# angle.net
KiCad netlist of a schematic drawn in EAGLE
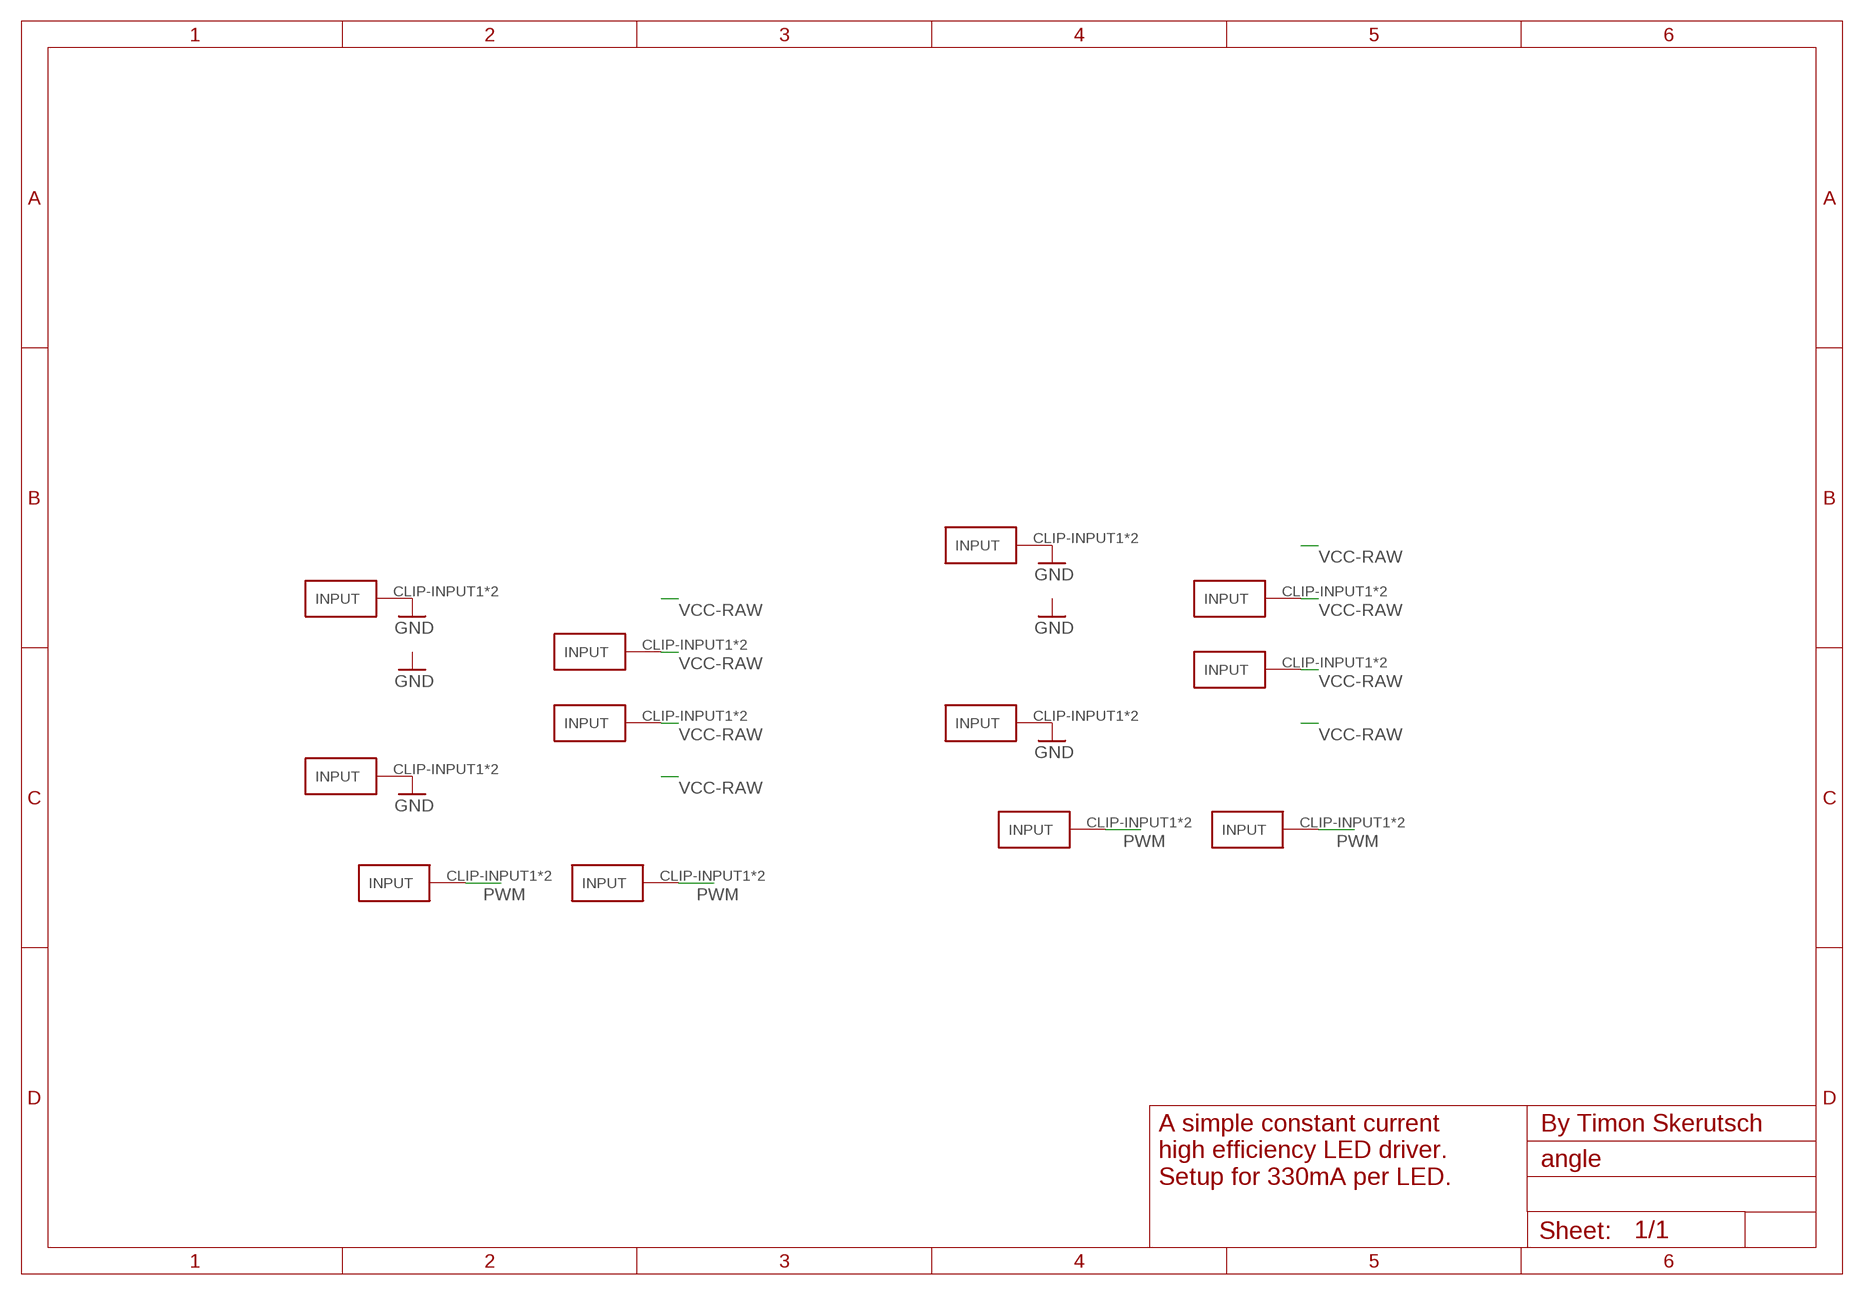
[diagram p0: schematic, sheet 1]

(export (version "E")
  (design (tool "Eeschema 10.0.6"))
  (components
    (comp (ref "GND-CLIP")
      (value "FUSE-HOLDER-5X20MM")
      (footprint "eagle-import:FUSE-HOLDER-5X20MM")
      (libsource (lib "eagle-import") (part "FUSE-HOLDER-5X20MM"))
    )
    (comp (ref "GND-CLIP1")
      (value "FUSE-HOLDER-5X20MM")
      (footprint "eagle-import:FUSE-HOLDER-5X20MM")
      (libsource (lib "eagle-import") (part "FUSE-HOLDER-5X20MM"))
    )
    (comp (ref "GND-CLIP2")
      (value "FUSE-HOLDER-5X20MM")
      (footprint "eagle-import:FUSE-HOLDER-5X20MM")
      (libsource (lib "eagle-import") (part "FUSE-HOLDER-5X20MM"))
    )
    (comp (ref "GND-CLIP3")
      (value "FUSE-HOLDER-5X20MM")
      (footprint "eagle-import:FUSE-HOLDER-5X20MM")
      (libsource (lib "eagle-import") (part "FUSE-HOLDER-5X20MM"))
    )
    (comp (ref "PWM-CLIP")
      (value "FUSE-HOLDER-5X20MM")
      (footprint "eagle-import:FUSE-HOLDER-5X20MM")
      (libsource (lib "eagle-import") (part "FUSE-HOLDER-5X20MM"))
    )
    (comp (ref "PWM-CLIP1")
      (value "FUSE-HOLDER-5X20MM")
      (footprint "eagle-import:FUSE-HOLDER-5X20MM")
      (libsource (lib "eagle-import") (part "FUSE-HOLDER-5X20MM"))
    )
    (comp (ref "PWM-CLIP2")
      (value "FUSE-HOLDER-5X20MM")
      (footprint "eagle-import:FUSE-HOLDER-5X20MM")
      (libsource (lib "eagle-import") (part "FUSE-HOLDER-5X20MM"))
    )
    (comp (ref "PWM-CLIP3")
      (value "FUSE-HOLDER-5X20MM")
      (footprint "eagle-import:FUSE-HOLDER-5X20MM")
      (libsource (lib "eagle-import") (part "FUSE-HOLDER-5X20MM"))
    )
    (comp (ref "VCC-CLIP")
      (value "FUSE-HOLDER-5X20MM")
      (footprint "eagle-import:FUSE-HOLDER-5X20MM")
      (libsource (lib "eagle-import") (part "FUSE-HOLDER-5X20MM"))
    )
    (comp (ref "VCC-CLIP1")
      (value "FUSE-HOLDER-5X20MM")
      (footprint "eagle-import:FUSE-HOLDER-5X20MM")
      (libsource (lib "eagle-import") (part "FUSE-HOLDER-5X20MM"))
    )
    (comp (ref "VCC-CLIP2")
      (value "FUSE-HOLDER-5X20MM")
      (footprint "eagle-import:FUSE-HOLDER-5X20MM")
      (libsource (lib "eagle-import") (part "FUSE-HOLDER-5X20MM"))
    )
    (comp (ref "VCC-CLIP3")
      (value "FUSE-HOLDER-5X20MM")
      (footprint "eagle-import:FUSE-HOLDER-5X20MM")
      (libsource (lib "eagle-import") (part "FUSE-HOLDER-5X20MM"))
    )
  )
  (nets
    (net (code "1") (name "/PWM") (class "Default")
      (node (ref "PWM-CLIP") (pin "CLIP-INPUT1") (pinfunction "INPUT_CLIP-INPUT1") (pintype "bidirectional"))
      (node (ref "PWM-CLIP") (pin "CLIP-INPUT2") (pinfunction "INPUT_CLIP-INPUT2") (pintype "bidirectional"))
      (node (ref "PWM-CLIP1") (pin "CLIP-INPUT1") (pinfunction "INPUT_CLIP-INPUT1") (pintype "bidirectional"))
      (node (ref "PWM-CLIP1") (pin "CLIP-INPUT2") (pinfunction "INPUT_CLIP-INPUT2") (pintype "bidirectional"))
      (node (ref "PWM-CLIP2") (pin "CLIP-INPUT1") (pinfunction "INPUT_CLIP-INPUT1") (pintype "bidirectional"))
      (node (ref "PWM-CLIP2") (pin "CLIP-INPUT2") (pinfunction "INPUT_CLIP-INPUT2") (pintype "bidirectional"))
      (node (ref "PWM-CLIP3") (pin "CLIP-INPUT1") (pinfunction "INPUT_CLIP-INPUT1") (pintype "bidirectional"))
      (node (ref "PWM-CLIP3") (pin "CLIP-INPUT2") (pinfunction "INPUT_CLIP-INPUT2") (pintype "bidirectional"))
    )
    (net (code "2") (name "/VCC-RAW") (class "Default")
      (node (ref "VCC-CLIP") (pin "CLIP-INPUT1") (pinfunction "INPUT_CLIP-INPUT1") (pintype "bidirectional"))
      (node (ref "VCC-CLIP") (pin "CLIP-INPUT2") (pinfunction "INPUT_CLIP-INPUT2") (pintype "bidirectional"))
      (node (ref "VCC-CLIP1") (pin "CLIP-INPUT1") (pinfunction "INPUT_CLIP-INPUT1") (pintype "bidirectional"))
      (node (ref "VCC-CLIP1") (pin "CLIP-INPUT2") (pinfunction "INPUT_CLIP-INPUT2") (pintype "bidirectional"))
      (node (ref "VCC-CLIP2") (pin "CLIP-INPUT1") (pinfunction "INPUT_CLIP-INPUT1") (pintype "bidirectional"))
      (node (ref "VCC-CLIP2") (pin "CLIP-INPUT2") (pinfunction "INPUT_CLIP-INPUT2") (pintype "bidirectional"))
      (node (ref "VCC-CLIP3") (pin "CLIP-INPUT1") (pinfunction "INPUT_CLIP-INPUT1") (pintype "bidirectional"))
      (node (ref "VCC-CLIP3") (pin "CLIP-INPUT2") (pinfunction "INPUT_CLIP-INPUT2") (pintype "bidirectional"))
    )
    (net (code "3") (name "GND") (class "Default")
      (node (ref "GND-CLIP") (pin "CLIP-INPUT1") (pinfunction "INPUT_CLIP-INPUT1") (pintype "bidirectional"))
      (node (ref "GND-CLIP") (pin "CLIP-INPUT2") (pinfunction "INPUT_CLIP-INPUT2") (pintype "bidirectional"))
      (node (ref "GND-CLIP1") (pin "CLIP-INPUT1") (pinfunction "INPUT_CLIP-INPUT1") (pintype "bidirectional"))
      (node (ref "GND-CLIP1") (pin "CLIP-INPUT2") (pinfunction "INPUT_CLIP-INPUT2") (pintype "bidirectional"))
      (node (ref "GND-CLIP2") (pin "CLIP-INPUT1") (pinfunction "INPUT_CLIP-INPUT1") (pintype "bidirectional"))
      (node (ref "GND-CLIP2") (pin "CLIP-INPUT2") (pinfunction "INPUT_CLIP-INPUT2") (pintype "bidirectional"))
      (node (ref "GND-CLIP3") (pin "CLIP-INPUT1") (pinfunction "INPUT_CLIP-INPUT1") (pintype "bidirectional"))
      (node (ref "GND-CLIP3") (pin "CLIP-INPUT2") (pinfunction "INPUT_CLIP-INPUT2") (pintype "bidirectional"))
    )
  )
)
